# schematic1_1.net
KiCad netlist of a schematic drawn in Altium Designer
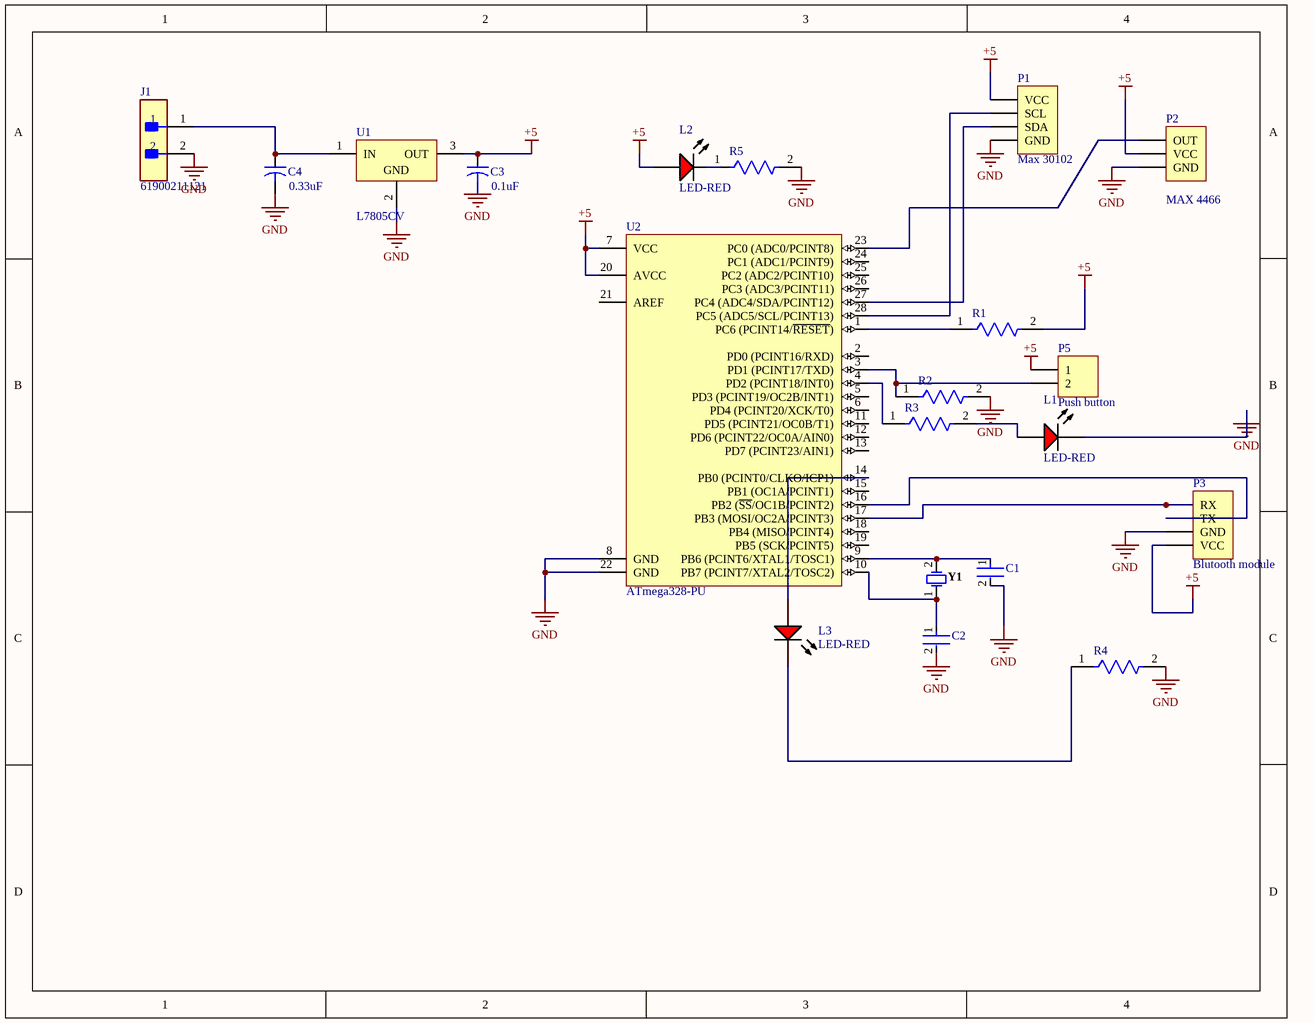
[diagram p0: schematic1(1).SchDoc]

(export (version "E")
  (design (tool "Eeschema 10.0.6"))
  (components
    (comp (ref "C1")
      (value "RCE5C1H220J0DBH03A")
      (footprint "FP-RCE0DB-MFG")
      (description "Cap Ceramic 22pF 50V C0G ±5% Radial 2.5mm +125°C Ammo Pack")
      (fields (field (name "TOLERANCE") "5%"))
      (libsource (lib "Altium Content Vault") (part "b4654b650e69147ec39a6b967a45e02"))
    )
    (comp (ref "C2")
      (value "RCE5C1H220J0DBH03A")
      (footprint "FP-RCE0DB-MFG")
      (description "Cap Ceramic 22pF 50V C0G ±5% Radial 2.5mm +125°C Ammo Pack")
      (fields (field (name "TOLERANCE") "5%"))
      (libsource (lib "Altium Content Vault") (part "b4654b650e69147ec39a6b967a45e02"))
    )
    (comp (ref "C3")
      (value "0.1uF")
      (footprint "CAPR5-4X5")
      (description "Capacitor")
      (fields (field (name "Comment") "Cap2") (field (name "PUBLISHER") "Altium Limited"))
      (libsource (lib "Miscellaneous Devices") (part "Cap2"))
    )
    (comp (ref "C4")
      (value "0.33uF")
      (footprint "CAPR5-4X5")
      (description "Capacitor")
      (fields (field (name "Comment") "Cap2") (field (name "PUBLISHER") "Altium Limited"))
      (libsource (lib "Miscellaneous Devices") (part "Cap2"))
    )
    (comp (ref "J1")
      (value "61900211121")
      (footprint "FP-61900211121-MFG")
      (description "CONN HEADER VERT 2POS 2.54MM")
      (libsource (lib "Altium Content Vault") (part "3bc925449376181038e59eaffc5286c"))
    )
    (comp (ref "L1")
      (value "LED-RED")
      (footprint "AVAG-HLMP-3301-2")
      (description "T-1 3/4 (5 mm) Diffused LED Lamp, 1.9 V, -40 to 100 degC, 2-Pin THD, RoHS, Bulk")
      (fields (field (name "MANUFACTURER") "Avago"))
      (libsource (lib "Altium Content Vault") (part "LED-RED-K1A2-2"))
    )
    (comp (ref "L2")
      (value "LED-RED")
      (footprint "AVAG-HLMP-3301-2")
      (description "T-1 3/4 (5 mm) Diffused LED Lamp, 1.9 V, -40 to 100 degC, 2-Pin THD, RoHS, Bulk")
      (fields (field (name "MANUFACTURER") "Avago"))
      (libsource (lib "Altium Content Vault") (part "LED-RED-K1A2-2"))
    )
    (comp (ref "L3")
      (value "LED-RED")
      (footprint "AVAG-HLMP-3301-2")
      (description "T-1 3/4 (5 mm) Diffused LED Lamp, 1.9 V, -40 to 100 degC, 2-Pin THD, RoHS, Bulk")
      (fields (field (name "MANUFACTURER") "Avago"))
      (libsource (lib "Altium Content Vault") (part "LED-RED-K1A2-2"))
    )
    (comp (ref "P1")
      (value "Max 30102")
      (footprint "HDR1X4")
      (description "Header, 4-Pin")
      (fields (field (name "PUBLISHER") "Altium Limited"))
      (libsource (lib "Miscellaneous Connectors") (part "Header 4"))
    )
    (comp (ref "P2")
      (value "MAX 4466")
      (footprint "HDR1X3")
      (description "Header, 3-Pin")
      (fields (field (name "PUBLISHER") "Altium Limited"))
      (libsource (lib "Miscellaneous Connectors") (part "Header 3"))
    )
    (comp (ref "P3")
      (value "Blutooth module")
      (footprint "HDR1X4")
      (description "Header, 4-Pin")
      (fields (field (name "PUBLISHER") "Altium Limited"))
      (libsource (lib "Miscellaneous Connectors") (part "Header 4"))
    )
    (comp (ref "P5")
      (value "Push button")
      (footprint "HDR1X2")
      (description "Header, 2-Pin")
      (fields (field (name "PUBLISHER") "Altium Limited"))
      (libsource (lib "Miscellaneous Connectors") (part "Header 2"))
    )
    (comp (ref "R1")
      (value "CF18JT10K0")
      (footprint "FP-CF18-MFG")
      (description "RES 10K OHM 1/8W 5% CF AXIAL")
      (fields
        (field (name "MANUFACTURER") "Stackpole Electronics")
        (field (name "OCTOPART") "https://octopart.com/cf18jt10k0-stackpole+electronics-19205642")
      )
      (libsource (lib "Altium Content Vault") (part "1029c3af85768c4190bb7ad29bc67b5"))
    )
    (comp (ref "R2")
      (value "CF18JT10K0")
      (footprint "FP-CF18-MFG")
      (description "RES 10K OHM 1/8W 5% CF AXIAL")
      (fields
        (field (name "MANUFACTURER") "Stackpole Electronics")
        (field (name "OCTOPART") "https://octopart.com/cf18jt10k0-stackpole+electronics-19205642")
      )
      (libsource (lib "Altium Content Vault") (part "1029c3af85768c4190bb7ad29bc67b5"))
    )
    (comp (ref "R3")
      (value "CF18JT10K0")
      (footprint "FP-CF18-MFG")
      (description "RES 10K OHM 1/8W 5% CF AXIAL")
      (fields
        (field (name "MANUFACTURER") "Stackpole Electronics")
        (field (name "OCTOPART") "https://octopart.com/cf18jt10k0-stackpole+electronics-19205642")
      )
      (libsource (lib "Altium Content Vault") (part "1029c3af85768c4190bb7ad29bc67b5"))
    )
    (comp (ref "R4")
      (value "CF18JT10K0")
      (footprint "FP-CF18-MFG")
      (description "RES 10K OHM 1/8W 5% CF AXIAL")
      (fields
        (field (name "MANUFACTURER") "Stackpole Electronics")
        (field (name "OCTOPART") "https://octopart.com/cf18jt10k0-stackpole+electronics-19205642")
      )
      (libsource (lib "Altium Content Vault") (part "1029c3af85768c4190bb7ad29bc67b5"))
    )
    (comp (ref "R5")
      (value "CF18JT10K0")
      (footprint "FP-CF18-MFG")
      (description "RES 10K OHM 1/8W 5% CF AXIAL")
      (fields
        (field (name "MANUFACTURER") "Stackpole Electronics")
        (field (name "OCTOPART") "https://octopart.com/cf18jt10k0-stackpole+electronics-19205642")
      )
      (libsource (lib "Altium Content Vault") (part "1029c3af85768c4190bb7ad29bc67b5"))
    )
    (comp (ref "U1")
      (value "L7805CV")
      (footprint "TO220")
      (description "Positive Voltage Regulator, 5V, 3-Pin TO-220")
      (libsource (lib "Altium Content Vault") (part "PM-REG-L4940-SIL3"))
    )
    (comp (ref "U2")
      (value "ATmega328-PU")
      (footprint "28P3")
      (libsource (lib "Altium Content Vault") (part "MC-8B-ATM48-IL28"))
    )
    (comp (ref "Y1")
      (value "FOXSLF/160-20")
      (footprint "FOX-FOXSLF160-20")
      (description "Resistance Weld Thru-Hole Crystal, 16 MHz, -20 to 70 degC, 2-Pin THD, RoHS, Bulk")
      (fields (field (name "TOLERANCE") "1%"))
      (libsource (lib "Altium Content Vault") (part "XTAL-1-2-2"))
    )
  )
  (nets
    (net (code "1") (name "+5") (class "Default")
      (node (ref "C3") (pin "1") (pinfunction "1_1") (pintype "passive"))
      (node (ref "L2") (pin "2") (pinfunction "A_2") (pintype "passive"))
      (node (ref "P1") (pin "1") (pinfunction "VCC_1") (pintype "passive"))
      (node (ref "P2") (pin "2") (pinfunction "VCC_2") (pintype "passive"))
      (node (ref "P3") (pin "4") (pinfunction "GND_4") (pintype "passive"))
      (node (ref "P5") (pin "1") (pinfunction "1_1") (pintype "passive"))
      (node (ref "R1") (pin "2") (pinfunction "2_2") (pintype "passive"))
      (node (ref "U1") (pin "3") (pinfunction "OUT_3") (pintype "power_in"))
      (node (ref "U2") (pin "20") (pinfunction "AVCC_20") (pintype "power_in"))
      (node (ref "U2") (pin "7") (pinfunction "VCC_7") (pintype "power_in"))
    )
    (net (code "2") (name "GND") (class "Default")
      (node (ref "C1") (pin "2") (pinfunction "2_2") (pintype "passive"))
      (node (ref "C2") (pin "2") (pinfunction "2_2") (pintype "passive"))
      (node (ref "C3") (pin "2") (pinfunction "2_2") (pintype "passive"))
      (node (ref "C4") (pin "2") (pinfunction "2_2") (pintype "passive"))
      (node (ref "J1") (pin "2") (pinfunction "2_2") (pintype "passive"))
      (node (ref "L1") (pin "1") (pinfunction "K_1") (pintype "passive"))
      (node (ref "P1") (pin "4") (pinfunction "GND_4") (pintype "passive"))
      (node (ref "P2") (pin "3") (pinfunction "GND_3") (pintype "passive"))
      (node (ref "P3") (pin "3") (pinfunction "SDA_3") (pintype "passive"))
      (node (ref "R2") (pin "2") (pinfunction "2_2") (pintype "passive"))
      (node (ref "R4") (pin "2") (pinfunction "2_2") (pintype "passive"))
      (node (ref "R5") (pin "2") (pinfunction "2_2") (pintype "passive"))
      (node (ref "U1") (pin "2") (pinfunction "GND_2") (pintype "power_in"))
      (node (ref "U2") (pin "22") (pinfunction "GND_22") (pintype "power_in"))
      (node (ref "U2") (pin "8") (pinfunction "GND_8") (pintype "power_in"))
    )
    (net (code "3") (name "Net-(L1-A)") (class "Default")
      (node (ref "L1") (pin "2") (pinfunction "A_2") (pintype "passive"))
      (node (ref "R3") (pin "2") (pinfunction "2_2") (pintype "passive"))
    )
    (net (code "4") (name "Net-(L2-K)") (class "Default")
      (node (ref "L2") (pin "1") (pinfunction "K_1") (pintype "passive"))
      (node (ref "R5") (pin "1") (pinfunction "1_1") (pintype "passive"))
    )
    (net (code "5") (name "Net-(L3-A)") (class "Default")
      (node (ref "L3") (pin "2") (pinfunction "A_2") (pintype "passive"))
      (node (ref "U2") (pin "14") (pinfunction "PB0_(PCINT0/CLKO/ICP1)_14") (pintype "bidirectional"))
    )
    (net (code "6") (name "Net-(L3-K)") (class "Default")
      (node (ref "L3") (pin "1") (pinfunction "K_1") (pintype "passive"))
      (node (ref "R4") (pin "1") (pinfunction "1_1") (pintype "passive"))
    )
    (net (code "7") (name "Net-(P1-SCL)") (class "Default")
      (node (ref "P1") (pin "2") (pinfunction "SCL_2") (pintype "passive"))
      (node (ref "U2") (pin "28") (pinfunction "PC5_(ADC5/SCL/PCINT13)_28") (pintype "bidirectional"))
    )
    (net (code "8") (name "Net-(P1-SDA)") (class "Default")
      (node (ref "P1") (pin "3") (pinfunction "SDA_3") (pintype "passive"))
      (node (ref "U2") (pin "27") (pinfunction "PC4_(ADC4/SDA/PCINT12)_27") (pintype "bidirectional"))
    )
    (net (code "9") (name "Net-(P2-OUT)") (class "Default")
      (node (ref "P2") (pin "1") (pinfunction "OUT_1") (pintype "passive"))
      (node (ref "U2") (pin "23") (pinfunction "PC0_(ADC0/PCINT8)_23") (pintype "bidirectional"))
    )
    (net (code "10") (name "Net-(P3-SCL)") (class "Default")
      (node (ref "P3") (pin "2") (pinfunction "SCL_2") (pintype "passive"))
      (node (ref "U2") (pin "16") (pinfunction "PB2_(~{SS}/OC1B/PCINT2)_16") (pintype "bidirectional"))
    )
    (net (code "11") (name "Net-(P3-VCC)") (class "Default")
      (node (ref "P3") (pin "1") (pinfunction "VCC_1") (pintype "passive"))
      (node (ref "U2") (pin "17") (pinfunction "PB3_(MOSI/OC2A/PCINT3)_17") (pintype "bidirectional"))
    )
    (net (code "12") (name "Net-(U1-IN)") (class "Default")
      (node (ref "C4") (pin "1") (pinfunction "1_1") (pintype "passive"))
      (node (ref "J1") (pin "1") (pinfunction "1_1") (pintype "passive"))
      (node (ref "U1") (pin "1") (pinfunction "IN_1") (pintype "power_in"))
    )
    (net (code "13") (name "Net-(U2-PB6_(PCINT6{slash}XTAL1{slash}TOSC1))") (class "Default")
      (node (ref "C1") (pin "1") (pinfunction "1_1") (pintype "passive"))
      (node (ref "U2") (pin "9") (pinfunction "PB6_(PCINT6/XTAL1/TOSC1)_9") (pintype "bidirectional"))
      (node (ref "Y1") (pin "2") (pinfunction "2_2") (pintype "passive"))
    )
    (net (code "14") (name "Net-(U2-PB7_(PCINT7{slash}XTAL2{slash}TOSC2))") (class "Default")
      (node (ref "C2") (pin "1") (pinfunction "1_1") (pintype "passive"))
      (node (ref "U2") (pin "10") (pinfunction "PB7_(PCINT7/XTAL2/TOSC2)_10") (pintype "bidirectional"))
      (node (ref "Y1") (pin "1") (pinfunction "1_1") (pintype "passive"))
    )
    (net (code "15") (name "Net-(U2-PC6_(PCINT14{slash}~{RESET}))") (class "Default")
      (node (ref "R1") (pin "1") (pinfunction "1_1") (pintype "passive"))
      (node (ref "U2") (pin "1") (pinfunction "PC6_(PCINT14/~{RESET})_1") (pintype "bidirectional"))
    )
    (net (code "16") (name "Net-(U2-PD1_(PCINT17{slash}TXD))") (class "Default")
      (node (ref "P5") (pin "2") (pinfunction "2_2") (pintype "passive"))
      (node (ref "R2") (pin "1") (pinfunction "1_1") (pintype "passive"))
      (node (ref "U2") (pin "3") (pinfunction "PD1_(PCINT17/TXD)_3") (pintype "bidirectional"))
    )
    (net (code "17") (name "Net-(U2-PD2_(PCINT18{slash}INT0))") (class "Default")
      (node (ref "R3") (pin "1") (pinfunction "1_1") (pintype "passive"))
      (node (ref "U2") (pin "4") (pinfunction "PD2_(PCINT18/INT0)_4") (pintype "bidirectional"))
    )
    (net (code "18") (name "unconnected-(U2-AREF-Pad21)") (class "Default")
      (node (ref "U2") (pin "21") (pinfunction "AREF_21") (pintype "power_in"))
    )
    (net (code "19") (name "unconnected-(U2-PB1_(OC1A{slash}PCINT1)-Pad15)") (class "Default")
      (node (ref "U2") (pin "15") (pinfunction "PB1_(OC1A/PCINT1)_15") (pintype "bidirectional"))
    )
    (net (code "20") (name "unconnected-(U2-PB4_(MISO{slash}PCINT4)-Pad18)") (class "Default")
      (node (ref "U2") (pin "18") (pinfunction "PB4_(MISO/PCINT4)_18") (pintype "bidirectional"))
    )
    (net (code "21") (name "unconnected-(U2-PB5_(SCK{slash}PCINT5)-Pad19)") (class "Default")
      (node (ref "U2") (pin "19") (pinfunction "PB5_(SCK/PCINT5)_19") (pintype "bidirectional"))
    )
    (net (code "22") (name "unconnected-(U2-PC1_(ADC1{slash}PCINT9)-Pad24)") (class "Default")
      (node (ref "U2") (pin "24") (pinfunction "PC1_(ADC1/PCINT9)_24") (pintype "bidirectional"))
    )
    (net (code "23") (name "unconnected-(U2-PC2_(ADC2{slash}PCINT10)-Pad25)") (class "Default")
      (node (ref "U2") (pin "25") (pinfunction "PC2_(ADC2/PCINT10)_25") (pintype "bidirectional"))
    )
    (net (code "24") (name "unconnected-(U2-PC3_(ADC3{slash}PCINT11)-Pad26)") (class "Default")
      (node (ref "U2") (pin "26") (pinfunction "PC3_(ADC3/PCINT11)_26") (pintype "bidirectional"))
    )
    (net (code "25") (name "unconnected-(U2-PD0_(PCINT16{slash}RXD)-Pad2)") (class "Default")
      (node (ref "U2") (pin "2") (pinfunction "PD0_(PCINT16/RXD)_2") (pintype "bidirectional"))
    )
    (net (code "26") (name "unconnected-(U2-PD3_(PCINT19{slash}OC2B{slash}INT1)-Pad5)") (class "Default")
      (node (ref "U2") (pin "5") (pinfunction "PD3_(PCINT19/OC2B/INT1)_5") (pintype "bidirectional"))
    )
    (net (code "27") (name "unconnected-(U2-PD4_(PCINT20{slash}XCK{slash}T0)-Pad6)") (class "Default")
      (node (ref "U2") (pin "6") (pinfunction "PD4_(PCINT20/XCK/T0)_6") (pintype "bidirectional"))
    )
    (net (code "28") (name "unconnected-(U2-PD5_(PCINT21{slash}OC0B{slash}T1)-Pad11)") (class "Default")
      (node (ref "U2") (pin "11") (pinfunction "PD5_(PCINT21/OC0B/T1)_11") (pintype "bidirectional"))
    )
    (net (code "29") (name "unconnected-(U2-PD6_(PCINT22{slash}OC0A{slash}AIN0)-Pad12)") (class "Default")
      (node (ref "U2") (pin "12") (pinfunction "PD6_(PCINT22/OC0A/AIN0)_12") (pintype "bidirectional"))
    )
    (net (code "30") (name "unconnected-(U2-PD7_(PCINT23{slash}AIN1)-Pad13)") (class "Default")
      (node (ref "U2") (pin "13") (pinfunction "PD7_(PCINT23/AIN1)_13") (pintype "bidirectional"))
    )
  )
)
